# untitled.net
KiCad netlist of a schematic drawn in EAGLE
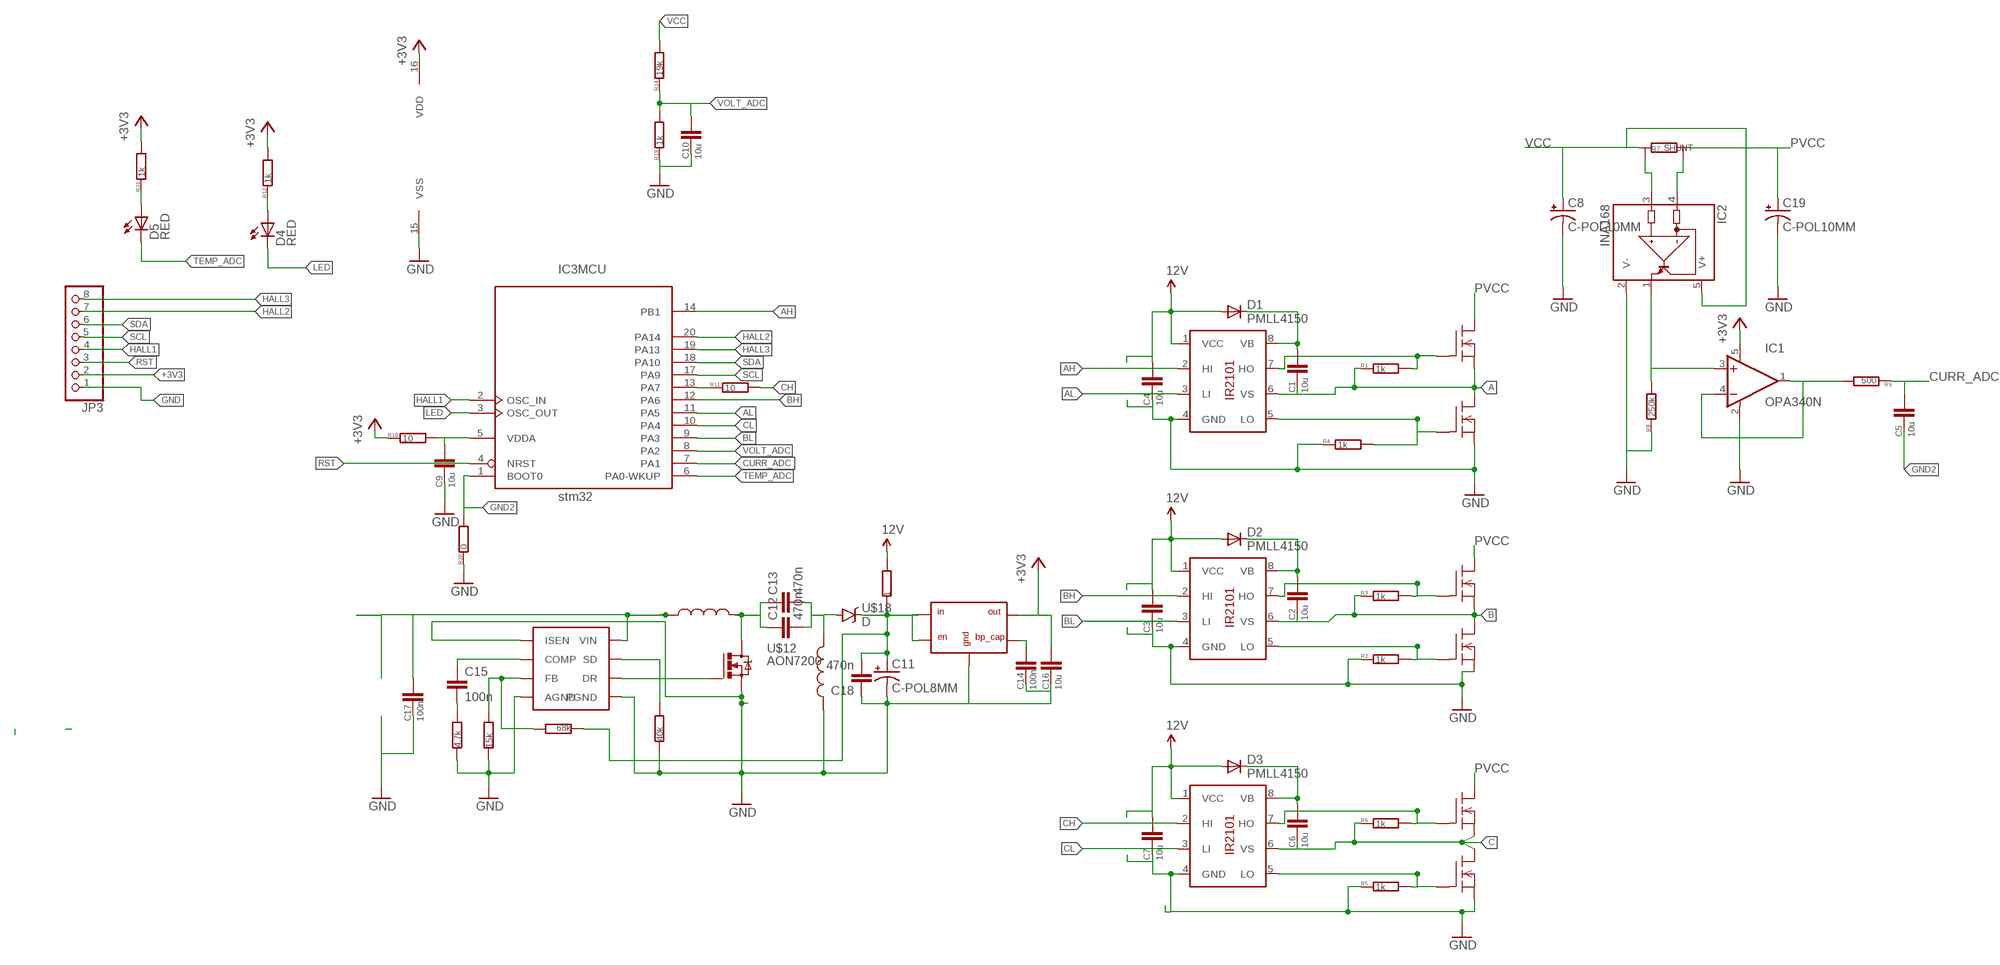
[diagram p0: schematic, sheet 1]

(export (version "E")
  (design (tool "Eeschema 10.0.6"))
  (components
    (comp (ref "C1")
      (value "10u")
      (footprint "eagle-import:C0805")
      (libsource (lib "eagle-import") (part "smalsmd_CC0805"))
    )
    (comp (ref "C2")
      (value "10u")
      (footprint "eagle-import:C0805")
      (libsource (lib "eagle-import") (part "smalsmd_CC0805"))
    )
    (comp (ref "C3")
      (value "10u")
      (footprint "eagle-import:C0805")
      (libsource (lib "eagle-import") (part "smalsmd_CC0805"))
    )
    (comp (ref "C4")
      (value "10u")
      (footprint "eagle-import:C0805")
      (libsource (lib "eagle-import") (part "smalsmd_CC0805"))
    )
    (comp (ref "C5")
      (value "10u")
      (footprint "eagle-import:C0603")
      (libsource (lib "eagle-import") (part "smalsmd_CC0603"))
    )
    (comp (ref "C6")
      (value "10u")
      (footprint "eagle-import:C0805")
      (libsource (lib "eagle-import") (part "smalsmd_CC0805"))
    )
    (comp (ref "C7")
      (value "10u")
      (footprint "eagle-import:C0805")
      (libsource (lib "eagle-import") (part "smalsmd_CC0805"))
    )
    (comp (ref "C8")
      (value "C-POL10MM")
      (footprint "eagle-import:PCAP10")
      (libsource (lib "eagle-import") (part "C-POL10MM"))
    )
    (comp (ref "C9")
      (value "10u")
      (footprint "eagle-import:C0805")
      (libsource (lib "eagle-import") (part "smalsmd_CC0805"))
    )
    (comp (ref "C10")
      (value "10u")
      (footprint "eagle-import:C0805")
      (libsource (lib "eagle-import") (part "smalsmd_CC0805"))
    )
    (comp (ref "C11")
      (value "C-POL8MM")
      (footprint "eagle-import:PCAP8")
      (libsource (lib "eagle-import") (part "C-POL8MM"))
    )
    (comp (ref "C12")
      (value "470n")
      (footprint "eagle-import:C1206")
      (libsource (lib "eagle-import") (part "CC1206"))
    )
    (comp (ref "C13")
      (value "470n")
      (footprint "eagle-import:C1206")
      (libsource (lib "eagle-import") (part "CC1206"))
    )
    (comp (ref "C14")
      (value "100n")
      (footprint "eagle-import:C0805")
      (libsource (lib "eagle-import") (part "smalsmd_CC0805"))
    )
    (comp (ref "C15")
      (value "100n")
      (footprint "eagle-import:C0603")
      (libsource (lib "eagle-import") (part "CC0603"))
    )
    (comp (ref "C16")
      (value "10u")
      (footprint "eagle-import:C0805")
      (libsource (lib "eagle-import") (part "smalsmd_CC0805"))
    )
    (comp (ref "C17")
      (value "100n")
      (footprint "eagle-import:C1206")
      (libsource (lib "eagle-import") (part "smalsmd_CC1206"))
    )
    (comp (ref "C18")
      (value "470n")
      (footprint "eagle-import:C0805")
      (libsource (lib "eagle-import") (part "CC0805"))
    )
    (comp (ref "C19")
      (value "C-POL10MM")
      (footprint "eagle-import:PCAP10")
      (libsource (lib "eagle-import") (part "C-POL10MM"))
    )
    (comp (ref "D1")
      (value "PMLL4150")
      (footprint "eagle-import:SOD80C")
      (libsource (lib "eagle-import") (part "PMLL4150"))
    )
    (comp (ref "D2")
      (value "PMLL4150")
      (footprint "eagle-import:SOD80C")
      (libsource (lib "eagle-import") (part "PMLL4150"))
    )
    (comp (ref "D3")
      (value "PMLL4150")
      (footprint "eagle-import:SOD80C")
      (libsource (lib "eagle-import") (part "PMLL4150"))
    )
    (comp (ref "D4")
      (value "RED")
      (footprint "eagle-import:0603-LED")
      (libsource (lib "eagle-import") (part "LED0603"))
    )
    (comp (ref "D5")
      (value "RED")
      (footprint "eagle-import:0603-LED")
      (libsource (lib "eagle-import") (part "LED0603"))
    )
    (comp (ref "IC1")
      (value "OPA340N")
      (footprint "eagle-import:SOT23-5")
      (fields (field (name "MPN") "OPA340NA/3KG4"))
      (libsource (lib "eagle-import") (part "OPA340N"))
    )
    (comp (ref "IC2")
      (value "INA168")
      (footprint "eagle-import:SOT23-5")
      (fields (field (name "MF") "TEXAS INSTRUMENTS") (field (name "MPN") "INA168NA/250"))
      (libsource (lib "eagle-import") (part "INA168"))
    )
    (comp (ref "IC3")
      (value "stm32")
      (footprint "eagle-import:TSSOP20-I")
      (libsource (lib "eagle-import") (part "STM32F030FP4"))
    )
    (comp (ref "IC4")
      (value "LM258DG")
      (footprint "eagle-import:SOT23-5L")
      (libsource (lib "eagle-import") (part "LM258DG"))
    )
    (comp (ref "JP3")
      (value "PINHD-1X8")
      (footprint "eagle-import:1X08")
      (libsource (lib "eagle-import") (part "PINHD-1X8"))
    )
    (comp (ref "Q1")
      (value "DFET")
      (footprint "eagle-import:DIRECT-FET")
      (libsource (lib "eagle-import") (part "DFET"))
    )
    (comp (ref "Q2")
      (value "DFET")
      (footprint "eagle-import:DIRECT-FET")
      (libsource (lib "eagle-import") (part "DFET"))
    )
    (comp (ref "Q3")
      (value "DFET")
      (footprint "eagle-import:DIRECT-FET")
      (libsource (lib "eagle-import") (part "DFET"))
    )
    (comp (ref "Q4")
      (value "DFET")
      (footprint "eagle-import:DIRECT-FET")
      (libsource (lib "eagle-import") (part "DFET"))
    )
    (comp (ref "Q5")
      (value "DFET")
      (footprint "eagle-import:DIRECT-FET")
      (libsource (lib "eagle-import") (part "DFET"))
    )
    (comp (ref "Q6")
      (value "DFET")
      (footprint "eagle-import:DIRECT-FET")
      (libsource (lib "eagle-import") (part "DFET"))
    )
    (comp (ref "R1")
      (value "1k")
      (footprint "eagle-import:0603")
      (libsource (lib "eagle-import") (part "smalsmd_R0603"))
    )
    (comp (ref "R2")
      (value "1k")
      (footprint "eagle-import:0603")
      (libsource (lib "eagle-import") (part "smalsmd_R0603"))
    )
    (comp (ref "R3")
      (value "1k")
      (footprint "eagle-import:0603")
      (libsource (lib "eagle-import") (part "smalsmd_R0603"))
    )
    (comp (ref "R4")
      (value "1k")
      (footprint "eagle-import:0603")
      (libsource (lib "eagle-import") (part "smalsmd_R0603"))
    )
    (comp (ref "R5")
      (value "1k")
      (footprint "eagle-import:0603")
      (libsource (lib "eagle-import") (part "smalsmd_R0603"))
    )
    (comp (ref "R6")
      (value "1k")
      (footprint "eagle-import:0603")
      (libsource (lib "eagle-import") (part "smalsmd_R0603"))
    )
    (comp (ref "R7")
      (value "SHUNT")
      (footprint "eagle-import:SHUNT")
      (libsource (lib "eagle-import") (part "SHUNT"))
    )
    (comp (ref "R8")
      (value "250k")
      (footprint "eagle-import:0603")
      (libsource (lib "eagle-import") (part "smalsmd_R0603"))
    )
    (comp (ref "R9")
      (value "500")
      (footprint "eagle-import:R0805")
      (libsource (lib "eagle-import") (part "smalsmd_R0805"))
    )
    (comp (ref "R10")
      (value "10")
      (footprint "eagle-import:0603")
      (libsource (lib "eagle-import") (part "smalsmd_R0603"))
    )
    (comp (ref "R11")
      (value "10")
      (footprint "eagle-import:R0805")
      (libsource (lib "eagle-import") (part "smalsmd_R0805"))
    )
    (comp (ref "R12")
      (value "1k")
      (footprint "eagle-import:0603")
      (libsource (lib "eagle-import") (part "smalsmd_R0603"))
    )
    (comp (ref "R13")
      (value "1")
      (footprint "eagle-import:R0805")
      (libsource (lib "eagle-import") (part "R0805"))
    )
    (comp (ref "R14")
      (value "19k")
      (footprint "eagle-import:R1206")
      (libsource (lib "eagle-import") (part "smalsmd_R1206"))
    )
    (comp (ref "R15")
      (value "40k")
      (footprint "eagle-import:0603")
      (libsource (lib "eagle-import") (part "R0603"))
    )
    (comp (ref "R16")
      (value "4.7k")
      (footprint "eagle-import:0603")
      (libsource (lib "eagle-import") (part "R0603"))
    )
    (comp (ref "R17")
      (value "15k")
      (footprint "eagle-import:0603")
      (libsource (lib "eagle-import") (part "R0603"))
    )
    (comp (ref "R18")
      (value "68k")
      (footprint "eagle-import:R0805")
      (libsource (lib "eagle-import") (part "R0805"))
    )
    (comp (ref "R19")
      (value "1k")
      (footprint "eagle-import:R0805")
      (libsource (lib "eagle-import") (part "smalsmd_R0805"))
    )
    (comp (ref "R20")
      (value "0")
      (footprint "eagle-import:R0805")
      (libsource (lib "eagle-import") (part "smalsmd_R0805"))
    )
    (comp (ref "R21")
      (value "1k")
      (footprint "eagle-import:0603")
      (libsource (lib "eagle-import") (part "smalsmd_R0603"))
    )
    (comp (ref "U$1")
      (value "IR2101")
      (footprint "eagle-import:SO08")
      (libsource (lib "eagle-import") (part "IR2101"))
    )
    (comp (ref "U$2")
      (value "IR2101")
      (footprint "eagle-import:SO08")
      (libsource (lib "eagle-import") (part "IR2101"))
    )
    (comp (ref "U$3")
      (value "IR2101")
      (footprint "eagle-import:SO08")
      (libsource (lib "eagle-import") (part "IR2101"))
    )
    (comp (ref "U$4")
      (value "INDUCTOR")
      (footprint "eagle-import:8MM_INDURCOR")
      (libsource (lib "eagle-import") (part "INDUCTOR"))
    )
    (comp (ref "U$5")
      (value "INDUCTOR")
      (footprint "eagle-import:8MM_INDURCOR")
      (libsource (lib "eagle-import") (part "INDUCTOR"))
    )
    (comp (ref "U$8")
      (value "LM3488")
      (footprint "eagle-import:S-PDSO-G8")
      (libsource (lib "eagle-import") (part "LM3488"))
    )
    (comp (ref "U$12")
      (value "AON7200")
      (footprint "eagle-import:DFN3X3")
      (libsource (lib "eagle-import") (part "AON7200"))
    )
    (comp (ref "U$18")
      (value "D")
      (footprint "eagle-import:SMA-DIODE")
      (libsource (lib "eagle-import") (part "SS14"))
    )
  )
  (nets
    (net (code "1") (name "+3V3") (class "Default")
      (node (ref "C16") (pin "1") (pinfunction "1_1") (pintype "passive"))
      (node (ref "IC1") (pin "5") (pinfunction "V+_5") (pintype "power_in"))
      (node (ref "IC3") (pin "16") (pinfunction "VDD_16") (pintype "power_in"))
      (node (ref "IC4") (pin "5") (pinfunction "OUT_5") (pintype "bidirectional"))
      (node (ref "JP3") (pin "2") (pinfunction "2_2") (pintype "passive"))
      (node (ref "R10") (pin "1") (pinfunction "1_1") (pintype "passive"))
      (node (ref "R12") (pin "2") (pinfunction "2_2") (pintype "passive"))
      (node (ref "R21") (pin "2") (pinfunction "2_2") (pintype "passive"))
    )
    (net (code "2") (name "/PVCC") (class "Default")
      (node (ref "C19") (pin "P$1") (pinfunction "+_P$1") (pintype "passive"))
      (node (ref "Q1") (pin "D") (pinfunction "D_D") (pintype "bidirectional"))
      (node (ref "Q1") (pin "D1") (pinfunction "D_D1") (pintype "bidirectional"))
      (node (ref "Q3") (pin "D") (pinfunction "D_D") (pintype "bidirectional"))
      (node (ref "Q3") (pin "D1") (pinfunction "D_D1") (pintype "bidirectional"))
      (node (ref "Q5") (pin "D") (pinfunction "D_D") (pintype "bidirectional"))
      (node (ref "Q5") (pin "D1") (pinfunction "D_D1") (pintype "bidirectional"))
      (node (ref "R7") (pin "P$2") (pinfunction "2_P$2") (pintype "passive"))
    )
    (net (code "3") (name "12V") (class "Default")
      (node (ref "C3") (pin "1") (pinfunction "1_1") (pintype "passive"))
      (node (ref "C4") (pin "1") (pinfunction "1_1") (pintype "passive"))
      (node (ref "C7") (pin "1") (pinfunction "1_1") (pintype "passive"))
      (node (ref "D1") (pin "A") (pinfunction "A_A") (pintype "passive"))
      (node (ref "D2") (pin "A") (pinfunction "A_A") (pintype "passive"))
      (node (ref "D3") (pin "A") (pinfunction "A_A") (pintype "passive"))
      (node (ref "R13") (pin "2") (pinfunction "2_2") (pintype "passive"))
      (node (ref "U$1") (pin "1") (pinfunction "VCC_1") (pintype "bidirectional"))
      (node (ref "U$2") (pin "1") (pinfunction "VCC_1") (pintype "bidirectional"))
      (node (ref "U$3") (pin "1") (pinfunction "VCC_1") (pintype "bidirectional"))
    )
    (net (code "4") (name "A") (class "Default")
      (node (ref "C1") (pin "2") (pinfunction "2_2") (pintype "passive"))
      (node (ref "Q1") (pin "S") (pinfunction "S_S") (pintype "bidirectional"))
      (node (ref "Q1") (pin "S1") (pinfunction "S_S1") (pintype "bidirectional"))
      (node (ref "Q2") (pin "D") (pinfunction "D_D") (pintype "bidirectional"))
      (node (ref "Q2") (pin "D1") (pinfunction "D_D1") (pintype "bidirectional"))
      (node (ref "R1") (pin "1") (pinfunction "1_1") (pintype "passive"))
      (node (ref "U$1") (pin "6") (pinfunction "VS_6") (pintype "bidirectional"))
    )
    (net (code "5") (name "AH") (class "Default")
      (node (ref "IC3") (pin "14") (pinfunction "PB1_14") (pintype "bidirectional"))
      (node (ref "U$1") (pin "2") (pinfunction "HI_2") (pintype "bidirectional"))
    )
    (net (code "6") (name "AL") (class "Default")
      (node (ref "IC3") (pin "11") (pinfunction "PA5_11") (pintype "bidirectional"))
      (node (ref "U$1") (pin "3") (pinfunction "LI_3") (pintype "bidirectional"))
    )
    (net (code "7") (name "B") (class "Default")
      (node (ref "C2") (pin "2") (pinfunction "2_2") (pintype "passive"))
      (node (ref "Q3") (pin "S") (pinfunction "S_S") (pintype "bidirectional"))
      (node (ref "Q3") (pin "S1") (pinfunction "S_S1") (pintype "bidirectional"))
      (node (ref "Q4") (pin "D") (pinfunction "D_D") (pintype "bidirectional"))
      (node (ref "Q4") (pin "D1") (pinfunction "D_D1") (pintype "bidirectional"))
      (node (ref "R3") (pin "1") (pinfunction "1_1") (pintype "passive"))
      (node (ref "U$2") (pin "6") (pinfunction "VS_6") (pintype "bidirectional"))
    )
    (net (code "8") (name "BH") (class "Default")
      (node (ref "IC3") (pin "12") (pinfunction "PA6_12") (pintype "bidirectional"))
      (node (ref "U$2") (pin "2") (pinfunction "HI_2") (pintype "bidirectional"))
    )
    (net (code "9") (name "BL") (class "Default")
      (node (ref "IC3") (pin "9") (pinfunction "PA3_9") (pintype "bidirectional"))
      (node (ref "U$2") (pin "3") (pinfunction "LI_3") (pintype "bidirectional"))
    )
    (net (code "10") (name "C") (class "Default")
      (node (ref "C6") (pin "2") (pinfunction "2_2") (pintype "passive"))
      (node (ref "Q5") (pin "S") (pinfunction "S_S") (pintype "bidirectional"))
      (node (ref "Q5") (pin "S1") (pinfunction "S_S1") (pintype "bidirectional"))
      (node (ref "Q6") (pin "D") (pinfunction "D_D") (pintype "bidirectional"))
      (node (ref "Q6") (pin "D1") (pinfunction "D_D1") (pintype "bidirectional"))
      (node (ref "R6") (pin "1") (pinfunction "1_1") (pintype "passive"))
      (node (ref "U$3") (pin "6") (pinfunction "VS_6") (pintype "bidirectional"))
    )
    (net (code "11") (name "CH") (class "Default")
      (node (ref "R11") (pin "2") (pinfunction "2_2") (pintype "passive"))
      (node (ref "U$3") (pin "2") (pinfunction "HI_2") (pintype "bidirectional"))
    )
    (net (code "12") (name "CL") (class "Default")
      (node (ref "IC3") (pin "10") (pinfunction "PA4_10") (pintype "bidirectional"))
      (node (ref "U$3") (pin "3") (pinfunction "LI_3") (pintype "bidirectional"))
    )
    (net (code "13") (name "CURR_ADC") (class "Default")
      (node (ref "C5") (pin "1") (pinfunction "1_1") (pintype "passive"))
      (node (ref "IC3") (pin "7") (pinfunction "PA1_7") (pintype "bidirectional"))
      (node (ref "R9") (pin "1") (pinfunction "1_1") (pintype "passive"))
    )
    (net (code "14") (name "GND") (class "Default")
      (node (ref "C10") (pin "2") (pinfunction "2_2") (pintype "passive"))
      (node (ref "C11") (pin "P$2") (pinfunction "-_P$2") (pintype "passive"))
      (node (ref "C14") (pin "2") (pinfunction "2_2") (pintype "passive"))
      (node (ref "C16") (pin "2") (pinfunction "2_2") (pintype "passive"))
      (node (ref "C17") (pin "2") (pinfunction "2_2") (pintype "passive"))
      (node (ref "C18") (pin "1") (pinfunction "1_1") (pintype "passive"))
      (node (ref "C19") (pin "P$2") (pinfunction "-_P$2") (pintype "passive"))
      (node (ref "C3") (pin "2") (pinfunction "2_2") (pintype "passive"))
      (node (ref "C4") (pin "2") (pinfunction "2_2") (pintype "passive"))
      (node (ref "C7") (pin "2") (pinfunction "2_2") (pintype "passive"))
      (node (ref "C8") (pin "P$2") (pinfunction "-_P$2") (pintype "passive"))
      (node (ref "C9") (pin "2") (pinfunction "2_2") (pintype "passive"))
      (node (ref "IC1") (pin "2") (pinfunction "V-_2") (pintype "power_in"))
      (node (ref "IC2") (pin "2") (pinfunction "V-_2") (pintype "power_in"))
      (node (ref "IC3") (pin "15") (pinfunction "VSS_15") (pintype "power_in"))
      (node (ref "IC4") (pin "2") (pinfunction "GND_2") (pintype "bidirectional"))
      (node (ref "JP3") (pin "1") (pinfunction "1_1") (pintype "passive"))
      (node (ref "Q2") (pin "S") (pinfunction "S_S") (pintype "bidirectional"))
      (node (ref "Q2") (pin "S1") (pinfunction "S_S1") (pintype "bidirectional"))
      (node (ref "Q4") (pin "S") (pinfunction "S_S") (pintype "bidirectional"))
      (node (ref "Q4") (pin "S1") (pinfunction "S_S1") (pintype "bidirectional"))
      (node (ref "Q6") (pin "S") (pinfunction "S_S") (pintype "bidirectional"))
      (node (ref "Q6") (pin "S1") (pinfunction "S_S1") (pintype "bidirectional"))
      (node (ref "R15") (pin "1") (pinfunction "1_1") (pintype "passive"))
      (node (ref "R16") (pin "1") (pinfunction "1_1") (pintype "passive"))
      (node (ref "R17") (pin "1") (pinfunction "1_1") (pintype "passive"))
      (node (ref "R19") (pin "1") (pinfunction "1_1") (pintype "passive"))
      (node (ref "R2") (pin "1") (pinfunction "1_1") (pintype "passive"))
      (node (ref "R20") (pin "1") (pinfunction "1_1") (pintype "passive"))
      (node (ref "R4") (pin "1") (pinfunction "1_1") (pintype "passive"))
      (node (ref "R5") (pin "1") (pinfunction "1_1") (pintype "passive"))
      (node (ref "R8") (pin "1") (pinfunction "1_1") (pintype "passive"))
      (node (ref "U$1") (pin "4") (pinfunction "GND_4") (pintype "bidirectional"))
      (node (ref "U$12") (pin "S:1") (pinfunction "S_S:1") (pintype "passive"))
      (node (ref "U$12") (pin "S:2") (pinfunction "S_S:2") (pintype "passive"))
      (node (ref "U$12") (pin "S:3") (pinfunction "S_S:3") (pintype "passive"))
      (node (ref "U$2") (pin "4") (pinfunction "GND_4") (pintype "bidirectional"))
      (node (ref "U$3") (pin "4") (pinfunction "GND_4") (pintype "bidirectional"))
      (node (ref "U$4") (pin "P$1") (pinfunction "P$1_P$1") (pintype "power_in"))
      (node (ref "U$8") (pin "1") (pinfunction "ISEN_1") (pintype "bidirectional"))
      (node (ref "U$8") (pin "4") (pinfunction "AGND_4") (pintype "bidirectional"))
      (node (ref "U$8") (pin "5") (pinfunction "PGND_5") (pintype "bidirectional"))
    )
    (net (code "15") (name "GND2") (class "Default")
      (node (ref "C5") (pin "2") (pinfunction "2_2") (pintype "passive"))
      (node (ref "IC3") (pin "1") (pinfunction "BOOT0_1") (pintype "input"))
      (node (ref "R20") (pin "2") (pinfunction "2_2") (pintype "passive"))
    )
    (net (code "16") (name "HALL1") (class "Default")
      (node (ref "IC3") (pin "2") (pinfunction "OSC_IN_2") (pintype "bidirectional"))
      (node (ref "JP3") (pin "4") (pinfunction "4_4") (pintype "passive"))
    )
    (net (code "17") (name "HALL2") (class "Default")
      (node (ref "IC3") (pin "20") (pinfunction "PA14_20") (pintype "bidirectional"))
      (node (ref "JP3") (pin "7") (pinfunction "7_7") (pintype "passive"))
    )
    (net (code "18") (name "HALL3") (class "Default")
      (node (ref "IC3") (pin "19") (pinfunction "PA13_19") (pintype "bidirectional"))
      (node (ref "JP3") (pin "8") (pinfunction "8_8") (pintype "passive"))
    )
    (net (code "19") (name "LED") (class "Default")
      (node (ref "D4") (pin "C") (pinfunction "C_C") (pintype "passive"))
      (node (ref "IC3") (pin "3") (pinfunction "OSC_OUT_3") (pintype "bidirectional"))
    )
    (net (code "20") (name "Net-(C11-+)") (class "Default")
      (node (ref "C11") (pin "P$1") (pinfunction "+_P$1") (pintype "passive"))
      (node (ref "C18") (pin "2") (pinfunction "2_2") (pintype "passive"))
      (node (ref "IC4") (pin "1") (pinfunction "IN_1") (pintype "bidirectional"))
      (node (ref "IC4") (pin "3") (pinfunction "EN_3") (pintype "bidirectional"))
      (node (ref "R13") (pin "1") (pinfunction "1_1") (pintype "passive"))
      (node (ref "R18") (pin "1") (pinfunction "1_1") (pintype "passive"))
      (node (ref "U$18") (pin "C") (pinfunction "C_C") (pintype "passive"))
    )
    (net (code "21") (name "Net-(C12-Pad1)") (class "Default")
      (node (ref "C12") (pin "1") (pinfunction "1_1") (pintype "passive"))
      (node (ref "C13") (pin "1") (pinfunction "1_1") (pintype "passive"))
      (node (ref "U$12") (pin "D") (pinfunction "D_D") (pintype "passive"))
      (node (ref "U$12") (pin "D:1") (pinfunction "D_D:1") (pintype "passive"))
      (node (ref "U$12") (pin "D:2") (pinfunction "D_D:2") (pintype "passive"))
      (node (ref "U$12") (pin "D:3") (pinfunction "D_D:3") (pintype "passive"))
      (node (ref "U$12") (pin "D:4") (pinfunction "D_D:4") (pintype "passive"))
      (node (ref "U$12") (pin "D:5") (pinfunction "D_D:5") (pintype "passive"))
      (node (ref "U$12") (pin "D:6") (pinfunction "D_D:6") (pintype "passive"))
      (node (ref "U$5") (pin "P$2") (pinfunction "P$2_P$2") (pintype "bidirectional"))
    )
    (net (code "22") (name "Net-(C12-Pad2)") (class "Default")
      (node (ref "C12") (pin "2") (pinfunction "2_2") (pintype "passive"))
      (node (ref "C13") (pin "2") (pinfunction "2_2") (pintype "passive"))
      (node (ref "U$18") (pin "A") (pinfunction "A_A") (pintype "passive"))
      (node (ref "U$4") (pin "P$2") (pinfunction "P$2_P$2") (pintype "bidirectional"))
    )
    (net (code "23") (name "Net-(C15-Pad2)") (class "Default")
      (node (ref "C15") (pin "2") (pinfunction "2_2") (pintype "passive"))
      (node (ref "R16") (pin "2") (pinfunction "2_2") (pintype "passive"))
    )
    (net (code "24") (name "Net-(D4-PadA)") (class "Default")
      (node (ref "D4") (pin "A") (pinfunction "A_A") (pintype "passive"))
      (node (ref "R12") (pin "1") (pinfunction "1_1") (pintype "passive"))
    )
    (net (code "25") (name "Net-(D5-PadA)") (class "Default")
      (node (ref "D5") (pin "A") (pinfunction "A_A") (pintype "passive"))
      (node (ref "R21") (pin "1") (pinfunction "1_1") (pintype "passive"))
    )
    (net (code "26") (name "Net-(IC1-+IN)") (class "Default")
      (node (ref "IC1") (pin "3") (pinfunction "+IN_3") (pintype "input"))
      (node (ref "IC2") (pin "1") (pinfunction "OUT_1") (pintype "output"))
      (node (ref "R8") (pin "2") (pinfunction "2_2") (pintype "passive"))
    )
    (net (code "27") (name "Net-(IC1--IN)") (class "Default")
      (node (ref "IC1") (pin "1") (pinfunction "OUT_1") (pintype "output"))
      (node (ref "IC1") (pin "4") (pinfunction "-IN_4") (pintype "input"))
      (node (ref "R9") (pin "2") (pinfunction "2_2") (pintype "passive"))
    )
    (net (code "28") (name "Net-(IC2-IN+)") (class "Default")
      (node (ref "IC2") (pin "3") (pinfunction "IN+_3") (pintype "input"))
      (node (ref "R7") (pin "P$3") (pinfunction "P$1_P$3") (pintype "bidirectional"))
    )
    (net (code "29") (name "Net-(IC2-IN-)") (class "Default")
      (node (ref "IC2") (pin "4") (pinfunction "IN-_4") (pintype "input"))
      (node (ref "R7") (pin "P$4") (pinfunction "P$2_P$4") (pintype "bidirectional"))
    )
    (net (code "30") (name "Net-(IC3A-PA7)") (class "Default")
      (node (ref "IC3") (pin "13") (pinfunction "PA7_13") (pintype "bidirectional"))
      (node (ref "R11") (pin "1") (pinfunction "1_1") (pintype "passive"))
    )
    (net (code "31") (name "Net-(IC3A-VDDA)") (class "Default")
      (node (ref "C9") (pin "1") (pinfunction "1_1") (pintype "passive"))
      (node (ref "IC3") (pin "5") (pinfunction "VDDA_5") (pintype "power_in"))
      (node (ref "R10") (pin "2") (pinfunction "2_2") (pintype "passive"))
    )
    (net (code "32") (name "Net-(IC4-CAP)") (class "Default")
      (node (ref "C14") (pin "1") (pinfunction "1_1") (pintype "passive"))
      (node (ref "IC4") (pin "4") (pinfunction "CAP_4") (pintype "bidirectional"))
    )
    (net (code "33") (name "Net-(Q1-G)") (class "Default")
      (node (ref "Q1") (pin "GATE") (pinfunction "G_GATE") (pintype "bidirectional"))
      (node (ref "R1") (pin "2") (pinfunction "2_2") (pintype "passive"))
      (node (ref "U$1") (pin "7") (pinfunction "HO_7") (pintype "bidirectional"))
    )
    (net (code "34") (name "Net-(Q2-G)") (class "Default")
      (node (ref "Q2") (pin "GATE") (pinfunction "G_GATE") (pintype "bidirectional"))
      (node (ref "R4") (pin "2") (pinfunction "2_2") (pintype "passive"))
      (node (ref "U$1") (pin "5") (pinfunction "LO_5") (pintype "bidirectional"))
    )
    (net (code "35") (name "Net-(Q3-G)") (class "Default")
      (node (ref "Q3") (pin "GATE") (pinfunction "G_GATE") (pintype "bidirectional"))
      (node (ref "R3") (pin "2") (pinfunction "2_2") (pintype "passive"))
      (node (ref "U$2") (pin "7") (pinfunction "HO_7") (pintype "bidirectional"))
    )
    (net (code "36") (name "Net-(Q4-G)") (class "Default")
      (node (ref "Q4") (pin "GATE") (pinfunction "G_GATE") (pintype "bidirectional"))
      (node (ref "R2") (pin "2") (pinfunction "2_2") (pintype "passive"))
      (node (ref "U$2") (pin "5") (pinfunction "LO_5") (pintype "bidirectional"))
    )
    (net (code "37") (name "Net-(Q5-G)") (class "Default")
      (node (ref "Q5") (pin "GATE") (pinfunction "G_GATE") (pintype "bidirectional"))
      (node (ref "R6") (pin "2") (pinfunction "2_2") (pintype "passive"))
      (node (ref "U$3") (pin "7") (pinfunction "HO_7") (pintype "bidirectional"))
    )
    (net (code "38") (name "Net-(Q6-G)") (class "Default")
      (node (ref "Q6") (pin "GATE") (pinfunction "G_GATE") (pintype "bidirectional"))
      (node (ref "R5") (pin "2") (pinfunction "2_2") (pintype "passive"))
      (node (ref "U$3") (pin "5") (pinfunction "LO_5") (pintype "bidirectional"))
    )
    (net (code "39") (name "Net-(U$1-VB)") (class "Default")
      (node (ref "C1") (pin "1") (pinfunction "1_1") (pintype "passive"))
      (node (ref "D1") (pin "C") (pinfunction "C_C") (pintype "passive"))
      (node (ref "U$1") (pin "8") (pinfunction "VB_8") (pintype "bidirectional"))
    )
    (net (code "40") (name "Net-(U$2-VB)") (class "Default")
      (node (ref "C2") (pin "1") (pinfunction "1_1") (pintype "passive"))
      (node (ref "D2") (pin "C") (pinfunction "C_C") (pintype "passive"))
      (node (ref "U$2") (pin "8") (pinfunction "VB_8") (pintype "bidirectional"))
    )
    (net (code "41") (name "Net-(U$3-VB)") (class "Default")
      (node (ref "C6") (pin "1") (pinfunction "1_1") (pintype "passive"))
      (node (ref "D3") (pin "C") (pinfunction "C_C") (pintype "passive"))
      (node (ref "U$3") (pin "8") (pinfunction "VB_8") (pintype "bidirectional"))
    )
    (net (code "42") (name "Net-(U$8-COMP)") (class "Default")
      (node (ref "C15") (pin "1") (pinfunction "1_1") (pintype "passive"))
      (node (ref "U$8") (pin "2") (pinfunction "COMP_2") (pintype "bidirectional"))
    )
    (net (code "43") (name "Net-(U$8-DR)") (class "Default")
      (node (ref "U$12") (pin "G") (pinfunction "G_G") (pintype "passive"))
      (node (ref "U$8") (pin "6") (pinfunction "DR_6") (pintype "bidirectional"))
    )
    (net (code "44") (name "Net-(U$8-FB)") (class "Default")
      (node (ref "R17") (pin "2") (pinfunction "2_2") (pintype "passive"))
      (node (ref "R18") (pin "2") (pinfunction "2_2") (pintype "passive"))
      (node (ref "U$8") (pin "3") (pinfunction "FB_3") (pintype "bidirectional"))
    )
    (net (code "45") (name "Net-(U$8-SD)") (class "Default")
      (node (ref "R15") (pin "2") (pinfunction "2_2") (pintype "passive"))
      (node (ref "U$8") (pin "7") (pinfunction "SD_7") (pintype "bidirectional"))
    )
    (net (code "46") (name "RST") (class "Default")
      (node (ref "IC3") (pin "4") (pinfunction "NRST_4") (pintype "bidirectional"))
      (node (ref "JP3") (pin "3") (pinfunction "3_3") (pintype "passive"))
    )
    (net (code "47") (name "SCL") (class "Default")
      (node (ref "IC3") (pin "17") (pinfunction "PA9_17") (pintype "bidirectional"))
      (node (ref "JP3") (pin "5") (pinfunction "5_5") (pintype "passive"))
    )
    (net (code "48") (name "SDA") (class "Default")
      (node (ref "IC3") (pin "18") (pinfunction "PA10_18") (pintype "bidirectional"))
      (node (ref "JP3") (pin "6") (pinfunction "6_6") (pintype "passive"))
    )
    (net (code "49") (name "TEMP_ADC") (class "Default")
      (node (ref "D5") (pin "C") (pinfunction "C_C") (pintype "passive"))
      (node (ref "IC3") (pin "6") (pinfunction "PA0-WKUP_6") (pintype "bidirectional"))
    )
    (net (code "50") (name "VCC") (class "Default")
      (node (ref "C17") (pin "1") (pinfunction "1_1") (pintype "passive"))
      (node (ref "C8") (pin "P$1") (pinfunction "+_P$1") (pintype "passive"))
      (node (ref "IC2") (pin "5") (pinfunction "V+_5") (pintype "power_in"))
      (node (ref "R14") (pin "2") (pinfunction "2_2") (pintype "passive"))
      (node (ref "R7") (pin "P$1") (pinfunction "1_P$1") (pintype "passive"))
      (node (ref "U$5") (pin "P$1") (pinfunction "P$1_P$1") (pintype "power_in"))
      (node (ref "U$8") (pin "8") (pinfunction "VIN_8") (pintype "bidirectional"))
    )
    (net (code "51") (name "VOLT_ADC") (class "Default")
      (node (ref "C10") (pin "1") (pinfunction "1_1") (pintype "passive"))
      (node (ref "IC3") (pin "8") (pinfunction "PA2_8") (pintype "bidirectional"))
      (node (ref "R14") (pin "1") (pinfunction "1_1") (pintype "passive"))
      (node (ref "R19") (pin "2") (pinfunction "2_2") (pintype "passive"))
    )
  )
)
